# coracao2.net
KiCad netlist of a schematic drawn in EAGLE
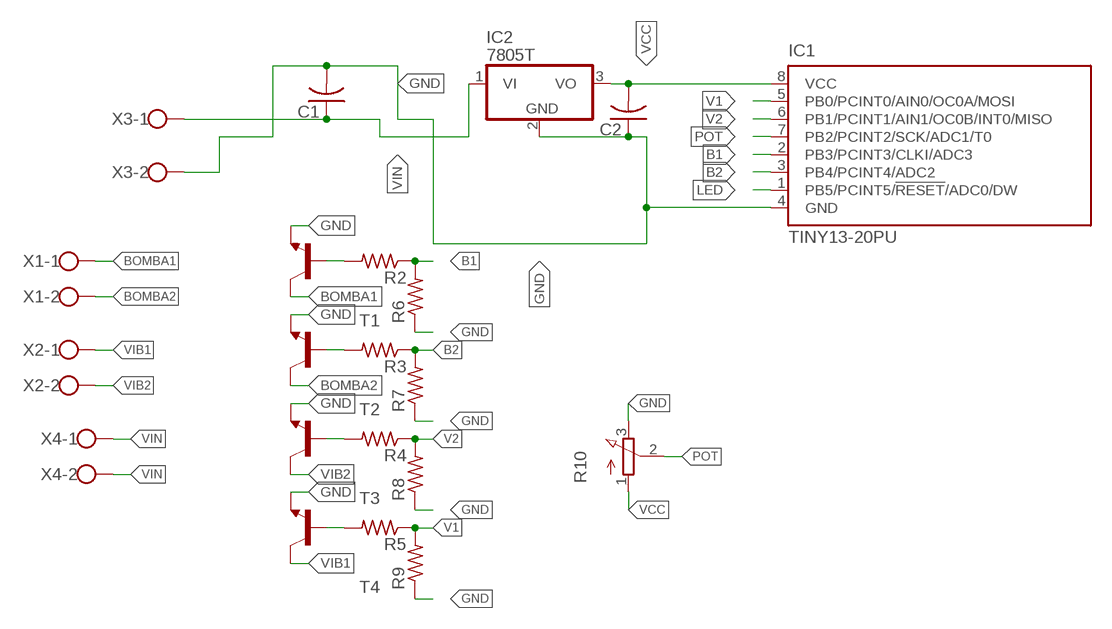
[diagram p0: schematic, sheet 1]

(export (version "E")
  (design (tool "Eeschema 10.0.6"))
  (components
    (comp (ref "C1")
      (value "C-US025-025X050")
      (footprint "eagle-import:C025-025X050")
      (libsource (lib "eagle-import") (part "C-US025-025X050"))
    )
    (comp (ref "C2")
      (value "C-US025-025X050")
      (footprint "eagle-import:C025-025X050")
      (libsource (lib "eagle-import") (part "C-US025-025X050"))
    )
    (comp (ref "IC1")
      (value "TINY13-20PU")
      (footprint "eagle-import:DIL08")
      (fields (field (name "MPN") "ATTINY13-20PU"))
      (libsource (lib "eagle-import") (part "TINY13PU-20"))
    )
    (comp (ref "IC2")
      (value "7805T")
      (footprint "eagle-import:TO220H")
      (libsource (lib "eagle-import") (part "78T05"))
    )
    (comp (ref "R2")
      (value "R-US_0207/9")
      (footprint "eagle-import:0207_9")
      (libsource (lib "eagle-import") (part "R-US_0207/9"))
    )
    (comp (ref "R3")
      (value "R-US_0207/9")
      (footprint "eagle-import:0207_9")
      (libsource (lib "eagle-import") (part "R-US_0207/9"))
    )
    (comp (ref "R4")
      (value "R-US_0207/9")
      (footprint "eagle-import:0207_9")
      (libsource (lib "eagle-import") (part "R-US_0207/9"))
    )
    (comp (ref "R5")
      (value "R-US_0207/9")
      (footprint "eagle-import:0207_9")
      (libsource (lib "eagle-import") (part "R-US_0207/9"))
    )
    (comp (ref "R6")
      (value "R-US_0207/9")
      (footprint "eagle-import:0207_9")
      (libsource (lib "eagle-import") (part "R-US_0207/9"))
    )
    (comp (ref "R7")
      (value "R-US_0207/9")
      (footprint "eagle-import:0207_9")
      (libsource (lib "eagle-import") (part "R-US_0207/9"))
    )
    (comp (ref "R8")
      (value "R-US_0207/9")
      (footprint "eagle-import:0207_9")
      (libsource (lib "eagle-import") (part "R-US_0207/9"))
    )
    (comp (ref "R9")
      (value "R-US_0207/9")
      (footprint "eagle-import:0207_9")
      (libsource (lib "eagle-import") (part "R-US_0207/9"))
    )
    (comp (ref "R10")
      (value "3RP/1610N")
      (footprint "eagle-import:3RP_1610N")
      (libsource (lib "eagle-import") (part "3RP/1610N"))
    )
    (comp (ref "T1")
      (value "-NPN-TO220V")
      (footprint "eagle-import:TO220V")
      (libsource (lib "eagle-import") (part "-NPN-TO220V"))
    )
    (comp (ref "T2")
      (value "-NPN-TO220V")
      (footprint "eagle-import:TO220V")
      (libsource (lib "eagle-import") (part "-NPN-TO220V"))
    )
    (comp (ref "T3")
      (value "-NPN-TO220V")
      (footprint "eagle-import:TO220V")
      (libsource (lib "eagle-import") (part "-NPN-TO220V"))
    )
    (comp (ref "T4")
      (value "-NPN-TO220V")
      (footprint "eagle-import:TO220V")
      (libsource (lib "eagle-import") (part "-NPN-TO220V"))
    )
    (comp (ref "X1")
      (value "W237-102")
      (footprint "eagle-import:W237-102")
      (fields (field (name "MPN") "237-102"))
      (libsource (lib "eagle-import") (part "W237-102"))
    )
    (comp (ref "X2")
      (value "W237-102")
      (footprint "eagle-import:W237-102")
      (fields (field (name "MPN") "237-102"))
      (libsource (lib "eagle-import") (part "W237-102"))
    )
    (comp (ref "X3")
      (value "W237-102")
      (footprint "eagle-import:W237-102")
      (fields (field (name "MPN") "237-102"))
      (libsource (lib "eagle-import") (part "W237-102"))
    )
    (comp (ref "X4")
      (value "W237-102")
      (footprint "eagle-import:W237-102")
      (fields (field (name "MPN") "237-102"))
      (libsource (lib "eagle-import") (part "W237-102"))
    )
  )
  (nets
    (net (code "1") (name "B1") (class "Default")
      (node (ref "IC1") (pin "2") (pinfunction "PB3/PCINT3/CLKI/ADC3_2") (pintype "bidirectional"))
      (node (ref "R2") (pin "1") (pinfunction "1_1") (pintype "passive"))
      (node (ref "R6") (pin "2") (pinfunction "2_2") (pintype "passive"))
    )
    (net (code "2") (name "B2") (class "Default")
      (node (ref "IC1") (pin "3") (pinfunction "PB4/PCINT4/ADC2_3") (pintype "bidirectional"))
      (node (ref "R3") (pin "1") (pinfunction "1_1") (pintype "passive"))
      (node (ref "R4") (pin "2") (pinfunction "2_2") (pintype "passive"))
      (node (ref "R7") (pin "2") (pinfunction "2_2") (pintype "passive"))
      (node (ref "T3") (pin "1") (pinfunction "B_1") (pintype "passive"))
    )
    (net (code "3") (name "BOMBA1") (class "Default")
      (node (ref "T1") (pin "2") (pinfunction "C_2") (pintype "passive"))
      (node (ref "X1") (pin "1") (pinfunction "KL_1") (pintype "passive"))
    )
    (net (code "4") (name "BOMBA2") (class "Default")
      (node (ref "T2") (pin "2") (pinfunction "C_2") (pintype "passive"))
      (node (ref "X1") (pin "2") (pinfunction "KL_2") (pintype "passive"))
    )
    (net (code "5") (name "GND") (class "Default")
      (node (ref "C1") (pin "2") (pinfunction "2_2") (pintype "passive"))
      (node (ref "C2") (pin "1") (pinfunction "1_1") (pintype "passive"))
      (node (ref "IC1") (pin "4") (pinfunction "GND_4") (pintype "power_in"))
      (node (ref "IC2") (pin "2") (pinfunction "GND_2") (pintype "passive"))
      (node (ref "R10") (pin "3") (pinfunction "E_3") (pintype "passive"))
      (node (ref "R6") (pin "1") (pinfunction "1_1") (pintype "passive"))
      (node (ref "R7") (pin "1") (pinfunction "1_1") (pintype "passive"))
      (node (ref "R8") (pin "1") (pinfunction "1_1") (pintype "passive"))
      (node (ref "R9") (pin "1") (pinfunction "1_1") (pintype "passive"))
      (node (ref "T1") (pin "3") (pinfunction "E_3") (pintype "passive"))
      (node (ref "T2") (pin "3") (pinfunction "E_3") (pintype "passive"))
      (node (ref "T3") (pin "3") (pinfunction "E_3") (pintype "passive"))
      (node (ref "T4") (pin "3") (pinfunction "E_3") (pintype "passive"))
      (node (ref "X3") (pin "2") (pinfunction "KL_2") (pintype "passive"))
    )
    (net (code "6") (name "LED") (class "Default")
      (node (ref "IC1") (pin "1") (pinfunction "PB5/PCINT5/~{RESET}/ADC0/DW_1") (pintype "bidirectional"))
    )
    (net (code "7") (name "Net-(T1-B)") (class "Default")
      (node (ref "R2") (pin "2") (pinfunction "2_2") (pintype "passive"))
      (node (ref "T1") (pin "1") (pinfunction "B_1") (pintype "passive"))
    )
    (net (code "8") (name "Net-(T2-B)") (class "Default")
      (node (ref "R3") (pin "2") (pinfunction "2_2") (pintype "passive"))
      (node (ref "T2") (pin "1") (pinfunction "B_1") (pintype "passive"))
    )
    (net (code "9") (name "Net-(T4-B)") (class "Default")
      (node (ref "R5") (pin "2") (pinfunction "2_2") (pintype "passive"))
      (node (ref "T4") (pin "1") (pinfunction "B_1") (pintype "passive"))
    )
    (net (code "10") (name "POT") (class "Default")
      (node (ref "IC1") (pin "7") (pinfunction "PB2/PCINT2/SCK/ADC1/T0_7") (pintype "bidirectional"))
      (node (ref "R10") (pin "2") (pinfunction "S_2") (pintype "passive"))
    )
    (net (code "11") (name "V1") (class "Default")
      (node (ref "IC1") (pin "5") (pinfunction "PB0/PCINT0/AIN0/OC0A/MOSI_5") (pintype "bidirectional"))
      (node (ref "R5") (pin "1") (pinfunction "1_1") (pintype "passive"))
      (node (ref "R9") (pin "2") (pinfunction "2_2") (pintype "passive"))
    )
    (net (code "12") (name "V2") (class "Default")
      (node (ref "IC1") (pin "6") (pinfunction "PB1/PCINT1/AIN1/OC0B/INT0/MISO_6") (pintype "bidirectional"))
      (node (ref "R4") (pin "1") (pinfunction "1_1") (pintype "passive"))
      (node (ref "R8") (pin "2") (pinfunction "2_2") (pintype "passive"))
    )
    (net (code "13") (name "VCC") (class "Default")
      (node (ref "C2") (pin "2") (pinfunction "2_2") (pintype "passive"))
      (node (ref "IC1") (pin "8") (pinfunction "VCC_8") (pintype "power_in"))
      (node (ref "IC2") (pin "3") (pinfunction "VO_3") (pintype "passive"))
      (node (ref "R10") (pin "1") (pinfunction "A_1") (pintype "passive"))
    )
    (net (code "14") (name "VIB1") (class "Default")
      (node (ref "T4") (pin "2") (pinfunction "C_2") (pintype "passive"))
      (node (ref "X2") (pin "1") (pinfunction "KL_1") (pintype "passive"))
    )
    (net (code "15") (name "VIB2") (class "Default")
      (node (ref "T3") (pin "2") (pinfunction "C_2") (pintype "passive"))
      (node (ref "X2") (pin "2") (pinfunction "KL_2") (pintype "passive"))
    )
    (net (code "16") (name "VIN") (class "Default")
      (node (ref "C1") (pin "1") (pinfunction "1_1") (pintype "passive"))
      (node (ref "IC2") (pin "1") (pinfunction "VI_1") (pintype "input"))
      (node (ref "X3") (pin "1") (pinfunction "KL_1") (pintype "passive"))
      (node (ref "X4") (pin "1") (pinfunction "KL_1") (pintype "passive"))
      (node (ref "X4") (pin "2") (pinfunction "KL_2") (pintype "passive"))
    )
  )
)
